# Track_em_V0_1.net
KiCad netlist of a schematic drawn in EAGLE
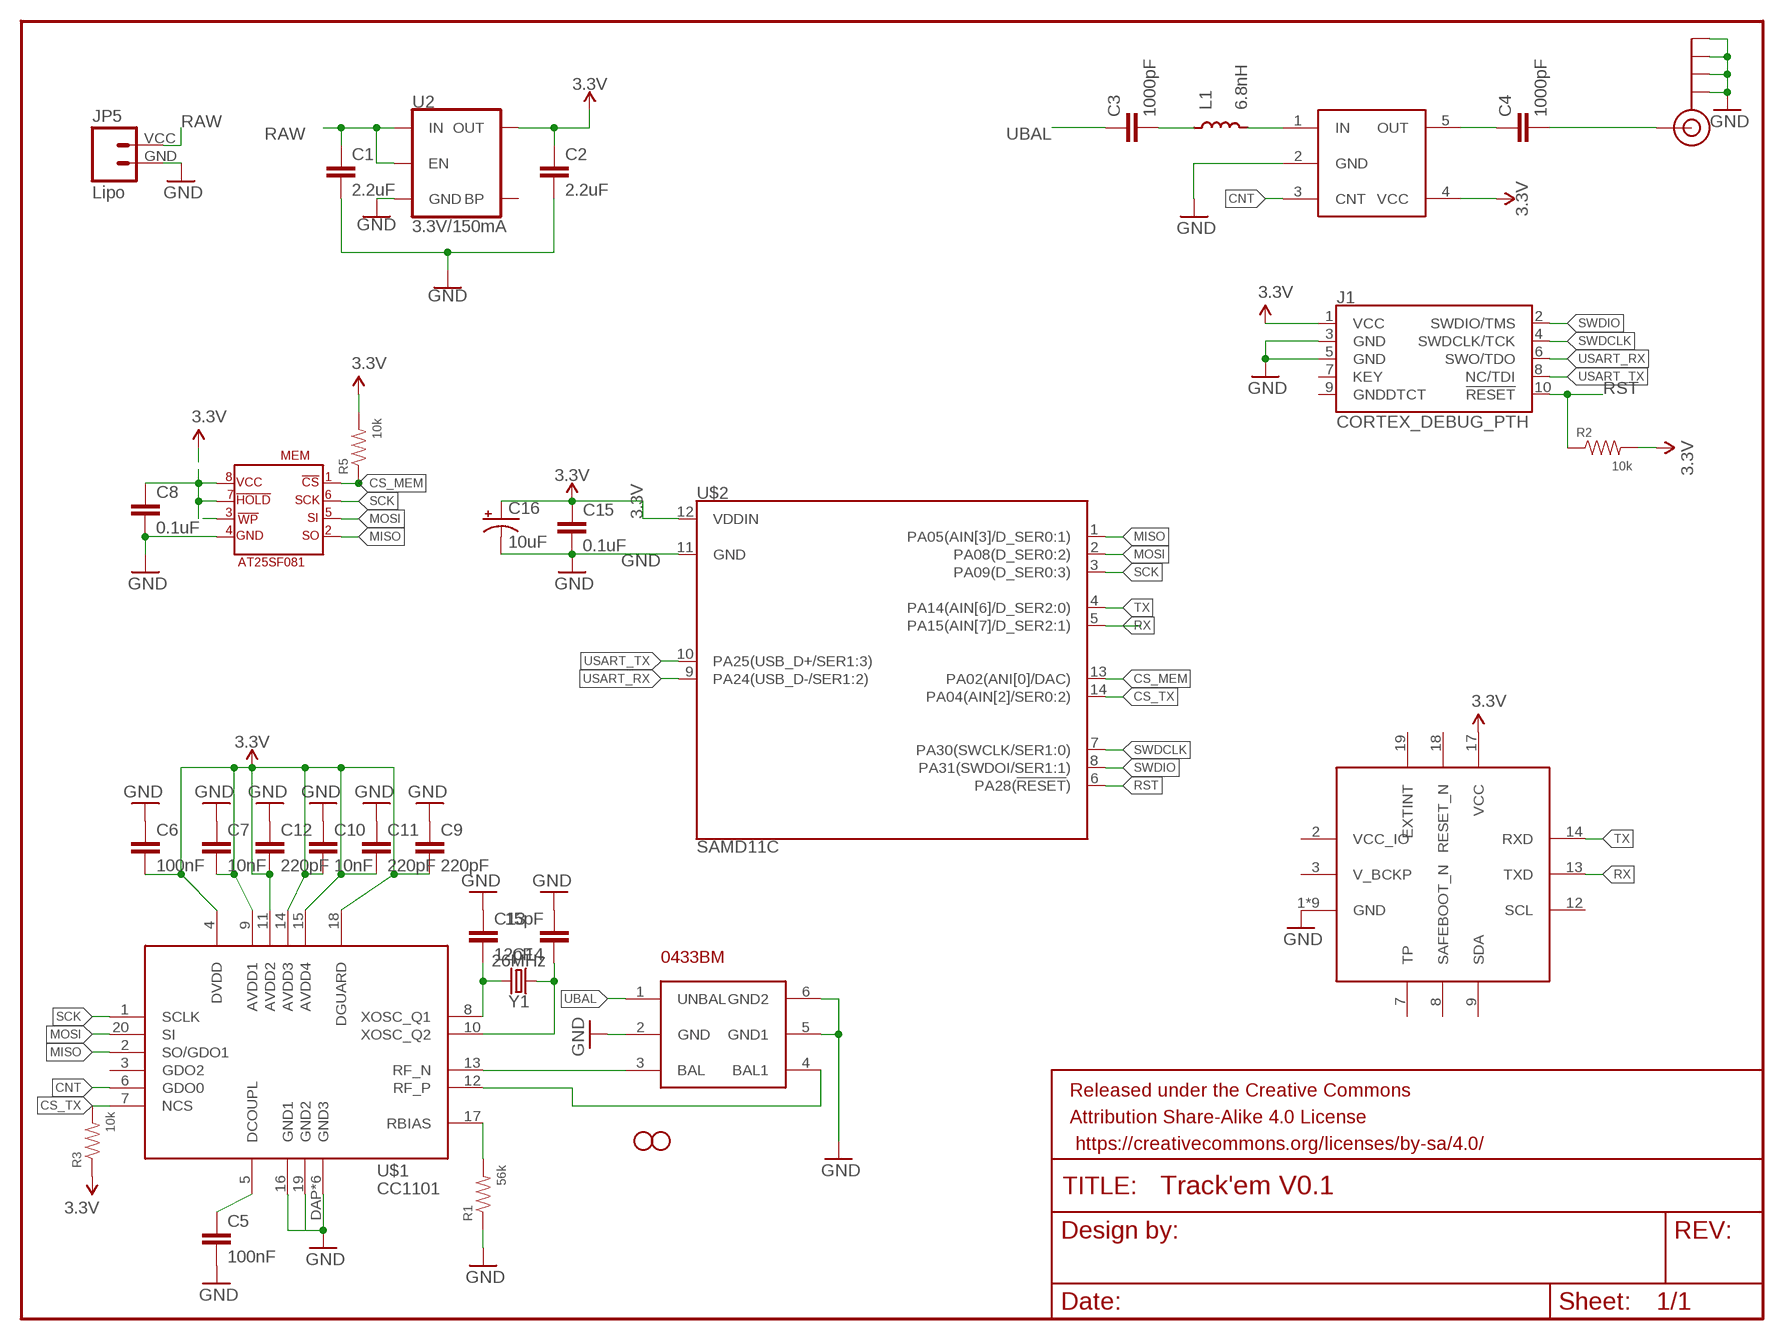
[diagram p0: schematic, sheet 1]

(export (version "E")
  (design (tool "Eeschema 10.0.6"))
  (components
    (comp (ref "C1")
      (value "2.2uF")
      (footprint "eagle-import:0603")
      (libsource (lib "eagle-import") (part "2.2UF-0603-10V-20%"))
    )
    (comp (ref "C2")
      (value "2.2uF")
      (footprint "eagle-import:0603")
      (libsource (lib "eagle-import") (part "2.2UF-0603-10V-20%"))
    )
    (comp (ref "C3")
      (value "1000pF")
      (footprint "eagle-import:0603")
      (libsource (lib "eagle-import") (part "2.2UF-0603-10V-20%"))
    )
    (comp (ref "C4")
      (value "1000pF")
      (footprint "eagle-import:0603")
      (libsource (lib "eagle-import") (part "2.2UF-0603-10V-20%"))
    )
    (comp (ref "C5")
      (value "100nF")
      (footprint "eagle-import:0402")
      (libsource (lib "eagle-import") (part "0.1UF-0402-16V-10%"))
    )
    (comp (ref "C6")
      (value "100nF")
      (footprint "eagle-import:0402")
      (libsource (lib "eagle-import") (part "0.1UF-0402-16V-10%"))
    )
    (comp (ref "C7")
      (value "10nF")
      (footprint "eagle-import:0402")
      (libsource (lib "eagle-import") (part "0.1UF-0402-16V-10%"))
    )
    (comp (ref "C8")
      (value "0.1uF")
      (footprint "eagle-import:0402")
      (libsource (lib "eagle-import") (part "0.1UF-0402-16V-10%"))
    )
    (comp (ref "C9")
      (value "220pF")
      (footprint "eagle-import:0402")
      (libsource (lib "eagle-import") (part "0.1UF-0402-16V-10%"))
    )
    (comp (ref "C10")
      (value "10nF")
      (footprint "eagle-import:0402")
      (libsource (lib "eagle-import") (part "0.1UF-0402-16V-10%"))
    )
    (comp (ref "C11")
      (value "220pF")
      (footprint "eagle-import:0402")
      (libsource (lib "eagle-import") (part "0.1UF-0402-16V-10%"))
    )
    (comp (ref "C12")
      (value "220pF")
      (footprint "eagle-import:0402")
      (libsource (lib "eagle-import") (part "0.1UF-0402-16V-10%"))
    )
    (comp (ref "C13")
      (value "12pF")
      (footprint "eagle-import:0402")
      (libsource (lib "eagle-import") (part "0.1UF-0402-16V-10%"))
    )
    (comp (ref "C14")
      (value "15pF")
      (footprint "eagle-import:0402")
      (libsource (lib "eagle-import") (part "0.1UF-0402-16V-10%"))
    )
    (comp (ref "C15")
      (value "0.1uF")
      (footprint "eagle-import:0402")
      (libsource (lib "eagle-import") (part "0.1UF-0402-16V-10%"))
    )
    (comp (ref "C16")
      (value "10uF")
      (footprint "eagle-import:0603-POL")
      (libsource (lib "eagle-import") (part "10UF-6.3V-20%(0603)(TANT){dblquote}"))
    )
    (comp (ref "FRAME1")
      (value "FRAME-LETTERNO_PACKAGE")
      (footprint "eagle-import:DUMMY")
      (fields (field (name "DESIGNER") "Nobody"))
      (libsource (lib "eagle-import") (part "FRAME-LETTERNO_PACKAGE"))
    )
    (comp (ref "H1")
      (value "STAND-OFFTIGHT")
      (footprint "eagle-import:STAND-OFF-TIGHT")
      (libsource (lib "eagle-import") (part "STAND-OFFTIGHT"))
    )
    (comp (ref "H2")
      (value "STAND-OFFTIGHT")
      (footprint "eagle-import:STAND-OFF-TIGHT")
      (libsource (lib "eagle-import") (part "STAND-OFFTIGHT"))
    )
    (comp (ref "IC1")
      (value "SAM-M8Q")
      (footprint "eagle-import:SAM-M8Q")
      (libsource (lib "eagle-import") (part "SAM-M8Q"))
    )
    (comp (ref "J$1")
      (value "SMA_EDGE")
      (footprint "eagle-import:SMA-EDGE")
      (libsource (lib "eagle-import") (part "SMA_EDGE"))
    )
    (comp (ref "J1")
      (value "CORTEX_DEBUG_PTH")
      (footprint "eagle-import:2X5-PTH-1.27MM")
      (libsource (lib "eagle-import") (part "CORTEX_DEBUG_PTH"))
    )
    (comp (ref "JP5")
      (value "Lipo")
      (footprint "eagle-import:JST-2-SMD-VERT")
      (libsource (lib "eagle-import") (part "M024UCON-15767"))
    )
    (comp (ref "L1")
      (value "6.8nH")
      (footprint "eagle-import:0603")
      (libsource (lib "eagle-import") (part "INDUCTOR0603"))
    )
    (comp (ref "MEM")
      (value "AT25SF081")
      (footprint "eagle-import:AT25SF081")
      (libsource (lib "eagle-import") (part "AT25SF081"))
    )
    (comp (ref "R1")
      (value "56k")
      (footprint "eagle-import:0402")
      (libsource (lib "eagle-import") (part "RESISTOR0402"))
    )
    (comp (ref "R2")
      (value "10k")
      (footprint "eagle-import:0402")
      (libsource (lib "eagle-import") (part "RESISTOR0402"))
    )
    (comp (ref "R3")
      (value "10k")
      (footprint "eagle-import:0402")
      (libsource (lib "eagle-import") (part "RESISTOR0402"))
    )
    (comp (ref "R5")
      (value "10k")
      (footprint "eagle-import:0402")
      (libsource (lib "eagle-import") (part "RESISTOR0402"))
    )
    (comp (ref "U$1")
      (value "CC1101")
      (footprint "eagle-import:CC1101")
      (libsource (lib "eagle-import") (part "CC1101"))
    )
    (comp (ref "U$2")
      (value "SAMD11C")
      (footprint "eagle-import:SAMD11C")
      (libsource (lib "eagle-import") (part "SAMD11C"))
    )
    (comp (ref "U$3")
      (value "0433BM15A0001")
      (footprint "eagle-import:0433BM15A0001")
      (libsource (lib "eagle-import") (part "0433BM15A0001"))
    )
    (comp (ref "U$4")
      (value "AN26018A")
      (footprint "eagle-import:AN26018A")
      (libsource (lib "eagle-import") (part "AN26018A"))
    )
    (comp (ref "U2")
      (value "3.3V/150mA")
      (footprint "eagle-import:SOT23-5")
      (libsource (lib "eagle-import") (part "V_REG_MIC52053.3V"))
    )
    (comp (ref "Y1")
      (value "26MHz")
      (footprint "eagle-import:CRYSTAL-SMD-3.2X2.5MM")
      (libsource (lib "eagle-import") (part "CRYSTALSMD-3.2X2.5"))
    )
  )
  (nets
    (net (code "1") (name "/RAW") (class "Default")
      (node (ref "C1") (pin "1") (pinfunction "1_1") (pintype "passive"))
      (node (ref "JP5") (pin "VCC") (pinfunction "2_VCC") (pintype "passive"))
      (node (ref "U2") (pin "1") (pinfunction "IN_1") (pintype "input"))
      (node (ref "U2") (pin "3") (pinfunction "EN_3") (pintype "input"))
    )
    (net (code "2") (name "3.3V") (class "Default")
      (node (ref "C10") (pin "2") (pinfunction "2_2") (pintype "passive"))
      (node (ref "C11") (pin "2") (pinfunction "2_2") (pintype "passive"))
      (node (ref "C12") (pin "2") (pinfunction "2_2") (pintype "passive"))
      (node (ref "C15") (pin "1") (pinfunction "1_1") (pintype "passive"))
      (node (ref "C16") (pin "A") (pinfunction "+_A") (pintype "passive"))
      (node (ref "C2") (pin "1") (pinfunction "1_1") (pintype "passive"))
      (node (ref "C6") (pin "2") (pinfunction "2_2") (pintype "passive"))
      (node (ref "C7") (pin "2") (pinfunction "2_2") (pintype "passive"))
      (node (ref "C8") (pin "1") (pinfunction "1_1") (pintype "passive"))
      (node (ref "C9") (pin "2") (pinfunction "2_2") (pintype "passive"))
      (node (ref "IC1") (pin "17") (pinfunction "VCC_17") (pintype "bidirectional"))
      (node (ref "J1") (pin "1") (pinfunction "VCC_1") (pintype "bidirectional"))
      (node (ref "MEM") (pin "!HOLD") (pinfunction "~{HOLD}_!HOLD") (pintype "bidirectional"))
      (node (ref "MEM") (pin "!WP") (pinfunction "~{WP}_!WP") (pintype "bidirectional"))
      (node (ref "MEM") (pin "VCC") (pinfunction "VCC_VCC") (pintype "bidirectional"))
      (node (ref "R2") (pin "2") (pinfunction "2_2") (pintype "passive"))
      (node (ref "R3") (pin "1") (pinfunction "1_1") (pintype "passive"))
      (node (ref "R5") (pin "2") (pinfunction "2_2") (pintype "passive"))
      (node (ref "U$1") (pin "11") (pinfunction "AVDD2_11") (pintype "bidirectional"))
      (node (ref "U$1") (pin "14") (pinfunction "AVDD3_14") (pintype "bidirectional"))
      (node (ref "U$1") (pin "15") (pinfunction "AVDD4_15") (pintype "bidirectional"))
      (node (ref "U$1") (pin "18") (pinfunction "DGUARD_18") (pintype "bidirectional"))
      (node (ref "U$1") (pin "4") (pinfunction "DVDD_4") (pintype "bidirectional"))
      (node (ref "U$1") (pin "9") (pinfunction "AVDD1_9") (pintype "bidirectional"))
      (node (ref "U$2") (pin "12") (pinfunction "VDDIN_12") (pintype "bidirectional"))
      (node (ref "U$4") (pin "4") (pinfunction "VCC_4") (pintype "bidirectional"))
      (node (ref "U2") (pin "5") (pinfunction "OUT_5") (pintype "passive"))
    )
    (net (code "3") (name "CNT") (class "Default")
      (node (ref "U$1") (pin "6") (pinfunction "GDO0_6") (pintype "bidirectional"))
      (node (ref "U$4") (pin "3") (pinfunction "CNT_3") (pintype "bidirectional"))
    )
    (net (code "4") (name "CS_MEM") (class "Default")
      (node (ref "MEM") (pin "!CS") (pinfunction "~{CS}_!CS") (pintype "bidirectional"))
      (node (ref "R5") (pin "1") (pinfunction "1_1") (pintype "passive"))
      (node (ref "U$2") (pin "13") (pinfunction "PA02(ANI[0]/DAC)_13") (pintype "bidirectional"))
    )
    (net (code "5") (name "CS_TX") (class "Default")
      (node (ref "R3") (pin "2") (pinfunction "2_2") (pintype "passive"))
      (node (ref "U$1") (pin "7") (pinfunction "NCS_7") (pintype "bidirectional"))
      (node (ref "U$2") (pin "14") (pinfunction "PA04(AIN[2]/SER0:2)_14") (pintype "bidirectional"))
    )
    (net (code "6") (name "GND") (class "Default")
      (node (ref "C1") (pin "2") (pinfunction "2_2") (pintype "passive"))
      (node (ref "C10") (pin "1") (pinfunction "1_1") (pintype "passive"))
      (node (ref "C11") (pin "1") (pinfunction "1_1") (pintype "passive"))
      (node (ref "C12") (pin "1") (pinfunction "1_1") (pintype "passive"))
      (node (ref "C13") (pin "1") (pinfunction "1_1") (pintype "passive"))
      (node (ref "C14") (pin "2") (pinfunction "2_2") (pintype "passive"))
      (node (ref "C15") (pin "2") (pinfunction "2_2") (pintype "passive"))
      (node (ref "C16") (pin "K") (pinfunction "-_K") (pintype "passive"))
      (node (ref "C2") (pin "2") (pinfunction "2_2") (pintype "passive"))
      (node (ref "C5") (pin "2") (pinfunction "2_2") (pintype "passive"))
      (node (ref "C6") (pin "1") (pinfunction "1_1") (pintype "passive"))
      (node (ref "C7") (pin "1") (pinfunction "1_1") (pintype "passive"))
      (node (ref "C8") (pin "2") (pinfunction "2_2") (pintype "passive"))
      (node (ref "C9") (pin "1") (pinfunction "1_1") (pintype "passive"))
      (node (ref "IC1") (pin "1") (pinfunction "GND_1") (pintype "bidirectional"))
      (node (ref "IC1") (pin "10") (pinfunction "GND_10") (pintype "bidirectional"))
      (node (ref "IC1") (pin "11") (pinfunction "GND_11") (pintype "bidirectional"))
      (node (ref "IC1") (pin "15") (pinfunction "GND_15") (pintype "bidirectional"))
      (node (ref "IC1") (pin "16") (pinfunction "GND_16") (pintype "bidirectional"))
      (node (ref "IC1") (pin "20") (pinfunction "GND_20") (pintype "bidirectional"))
      (node (ref "IC1") (pin "4") (pinfunction "GND_4") (pintype "bidirectional"))
      (node (ref "IC1") (pin "5") (pinfunction "GND_5") (pintype "bidirectional"))
      (node (ref "IC1") (pin "6") (pinfunction "GND_6") (pintype "bidirectional"))
      (node (ref "J$1") (pin "GND@0") (pinfunction "GND_GND@0") (pintype "bidirectional"))
      (node (ref "J$1") (pin "GND@1") (pinfunction "GND_GND@1") (pintype "bidirectional"))
      (node (ref "J$1") (pin "GND@2") (pinfunction "GND_GND@2") (pintype "bidirectional"))
      (node (ref "J$1") (pin "GND@3") (pinfunction "GND_GND@3") (pintype "bidirectional"))
      (node (ref "J1") (pin "3") (pinfunction "GND_3") (pintype "bidirectional"))
      (node (ref "J1") (pin "5") (pinfunction "GND_5") (pintype "bidirectional"))
      (node (ref "JP5") (pin "GND") (pinfunction "1_GND") (pintype "passive"))
      (node (ref "MEM") (pin "GND") (pinfunction "GND_GND") (pintype "bidirectional"))
      (node (ref "R1") (pin "1") (pinfunction "1_1") (pintype "passive"))
      (node (ref "U$1") (pin "16") (pinfunction "GND1_16") (pintype "bidirectional"))
      (node (ref "U$1") (pin "19") (pinfunction "GND2_19") (pintype "bidirectional"))
      (node (ref "U$1") (pin "DAP") (pinfunction "GND3_DAP") (pintype "bidirectional"))
      (node (ref "U$1") (pin "P$1") (pinfunction "GND3_P$1") (pintype "bidirectional"))
      (node (ref "U$1") (pin "P$2") (pinfunction "GND3_P$2") (pintype "bidirectional"))
      (node (ref "U$1") (pin "P$3") (pinfunction "GND3_P$3") (pintype "bidirectional"))
      (node (ref "U$1") (pin "P$4") (pinfunction "GND3_P$4") (pintype "bidirectional"))
      (node (ref "U$1") (pin "P$5") (pinfunction "GND3_P$5") (pintype "bidirectional"))
      (node (ref "U$2") (pin "11") (pinfunction "GND_11") (pintype "bidirectional"))
      (node (ref "U$3") (pin "2") (pinfunction "GND_2") (pintype "bidirectional"))
      (node (ref "U$3") (pin "5") (pinfunction "GND1_5") (pintype "bidirectional"))
      (node (ref "U$3") (pin "6") (pinfunction "GND2_6") (pintype "bidirectional"))
      (node (ref "U$4") (pin "2") (pinfunction "GND_2") (pintype "bidirectional"))
      (node (ref "U2") (pin "2") (pinfunction "GND_2") (pintype "input"))
    )
    (net (code "7") (name "MISO") (class "Default")
      (node (ref "MEM") (pin "SO") (pinfunction "SO_SO") (pintype "bidirectional"))
      (node (ref "U$1") (pin "2") (pinfunction "SO/GDO1_2") (pintype "bidirectional"))
      (node (ref "U$2") (pin "1") (pinfunction "PA05(AIN[3]/D_SER0:1)_1") (pintype "bidirectional"))
    )
    (net (code "8") (name "MOSI") (class "Default")
      (node (ref "MEM") (pin "SI") (pinfunction "SI_SI") (pintype "bidirectional"))
      (node (ref "U$1") (pin "20") (pinfunction "SI_20") (pintype "bidirectional"))
      (node (ref "U$2") (pin "2") (pinfunction "PA08(D_SER0:2)_2") (pintype "bidirectional"))
    )
    (net (code "9") (name "Net-(C3-Pad2)") (class "Default")
      (node (ref "C3") (pin "2") (pinfunction "2_2") (pintype "passive"))
      (node (ref "L1") (pin "1") (pinfunction "1_1") (pintype "passive"))
    )
    (net (code "10") (name "Net-(J$1-SIGNAL)") (class "Default")
      (node (ref "C4") (pin "2") (pinfunction "2_2") (pintype "passive"))
      (node (ref "J$1") (pin "SIG") (pinfunction "SIGNAL_SIG") (pintype "bidirectional"))
    )
    (net (code "11") (name "Net-(U$1-DCOUPL)") (class "Default")
      (node (ref "C5") (pin "1") (pinfunction "1_1") (pintype "passive"))
      (node (ref "U$1") (pin "5") (pinfunction "DCOUPL_5") (pintype "bidirectional"))
    )
    (net (code "12") (name "Net-(U$1-RBIAS)") (class "Default")
      (node (ref "R1") (pin "2") (pinfunction "2_2") (pintype "passive"))
      (node (ref "U$1") (pin "17") (pinfunction "RBIAS_17") (pintype "bidirectional"))
    )
    (net (code "13") (name "Net-(U$1-RF_N)") (class "Default")
      (node (ref "U$1") (pin "13") (pinfunction "RF_N_13") (pintype "bidirectional"))
      (node (ref "U$3") (pin "3") (pinfunction "BAL_3") (pintype "bidirectional"))
    )
    (net (code "14") (name "Net-(U$1-RF_P)") (class "Default")
      (node (ref "U$1") (pin "12") (pinfunction "RF_P_12") (pintype "bidirectional"))
      (node (ref "U$3") (pin "4") (pinfunction "BAL1_4") (pintype "bidirectional"))
    )
    (net (code "15") (name "Net-(U$1-XOSC_Q1)") (class "Default")
      (node (ref "C13") (pin "2") (pinfunction "2_2") (pintype "passive"))
      (node (ref "U$1") (pin "8") (pinfunction "XOSC_Q1_8") (pintype "bidirectional"))
      (node (ref "Y1") (pin "3") (pinfunction "2_3") (pintype "passive"))
    )
    (net (code "16") (name "Net-(U$1-XOSC_Q2)") (class "Default")
      (node (ref "C14") (pin "1") (pinfunction "1_1") (pintype "passive"))
      (node (ref "U$1") (pin "10") (pinfunction "XOSC_Q2_10") (pintype "bidirectional"))
      (node (ref "Y1") (pin "1") (pinfunction "1_1") (pintype "passive"))
    )
    (net (code "17") (name "Net-(U$4-IN)") (class "Default")
      (node (ref "L1") (pin "2") (pinfunction "2_2") (pintype "passive"))
      (node (ref "U$4") (pin "1") (pinfunction "IN_1") (pintype "bidirectional"))
    )
    (net (code "18") (name "Net-(U$4-OUT)") (class "Default")
      (node (ref "C4") (pin "1") (pinfunction "1_1") (pintype "passive"))
      (node (ref "U$4") (pin "5") (pinfunction "OUT_5") (pintype "bidirectional"))
    )
    (net (code "19") (name "RST") (class "Default")
      (node (ref "J1") (pin "10") (pinfunction "~{RESET}_10") (pintype "bidirectional"))
      (node (ref "R2") (pin "1") (pinfunction "1_1") (pintype "passive"))
      (node (ref "U$2") (pin "6") (pinfunction "PA28(~{RESET})_6") (pintype "bidirectional"))
    )
    (net (code "20") (name "RX") (class "Default")
      (node (ref "IC1") (pin "13") (pinfunction "TXD_13") (pintype "bidirectional"))
      (node (ref "U$2") (pin "5") (pinfunction "PA15(AIN[7]/D_SER2:1)_5") (pintype "bidirectional"))
    )
    (net (code "21") (name "SCK") (class "Default")
      (node (ref "MEM") (pin "SCK") (pinfunction "SCK_SCK") (pintype "bidirectional"))
      (node (ref "U$1") (pin "1") (pinfunction "SCLK_1") (pintype "bidirectional"))
      (node (ref "U$2") (pin "3") (pinfunction "PA09(D_SER0:3)_3") (pintype "bidirectional"))
    )
    (net (code "22") (name "SWDCLK") (class "Default")
      (node (ref "J1") (pin "4") (pinfunction "SWDCLK/TCK_4") (pintype "bidirectional"))
      (node (ref "U$2") (pin "7") (pinfunction "PA30(SWCLK/SER1:0)_7") (pintype "bidirectional"))
    )
    (net (code "23") (name "SWDIO") (class "Default")
      (node (ref "J1") (pin "2") (pinfunction "SWDIO/TMS_2") (pintype "bidirectional"))
      (node (ref "U$2") (pin "8") (pinfunction "PA31(SWDOI/SER1:1)_8") (pintype "bidirectional"))
    )
    (net (code "24") (name "TX") (class "Default")
      (node (ref "IC1") (pin "14") (pinfunction "RXD_14") (pintype "bidirectional"))
      (node (ref "U$2") (pin "4") (pinfunction "PA14(AIN[6]/D_SER2:0)_4") (pintype "bidirectional"))
    )
    (net (code "25") (name "UBAL") (class "Default")
      (node (ref "C3") (pin "1") (pinfunction "1_1") (pintype "passive"))
      (node (ref "U$3") (pin "1") (pinfunction "UNBAL_1") (pintype "bidirectional"))
    )
    (net (code "26") (name "USART_RX") (class "Default")
      (node (ref "J1") (pin "6") (pinfunction "SWO/TDO_6") (pintype "bidirectional"))
      (node (ref "U$2") (pin "9") (pinfunction "PA24(USB_D-/SER1:2)_9") (pintype "bidirectional"))
    )
    (net (code "27") (name "USART_TX") (class "Default")
      (node (ref "J1") (pin "8") (pinfunction "NC/TDI_8") (pintype "bidirectional"))
      (node (ref "U$2") (pin "10") (pinfunction "PA25(USB_D+/SER1:3)_10") (pintype "bidirectional"))
    )
    (net (code "28") (name "unconnected-(IC1-EXTINT-Pad19)") (class "Default")
      (node (ref "IC1") (pin "19") (pinfunction "EXTINT_19") (pintype "bidirectional"))
    )
    (net (code "29") (name "unconnected-(IC1-RESET_N-Pad18)") (class "Default")
      (node (ref "IC1") (pin "18") (pinfunction "RESET_N_18") (pintype "bidirectional"))
    )
    (net (code "30") (name "unconnected-(IC1-SAFEBOOT_N-Pad8)") (class "Default")
      (node (ref "IC1") (pin "8") (pinfunction "SAFEBOOT_N_8") (pintype "bidirectional"))
    )
    (net (code "31") (name "unconnected-(IC1-SCL-Pad12)") (class "Default")
      (node (ref "IC1") (pin "12") (pinfunction "SCL_12") (pintype "bidirectional"))
    )
    (net (code "32") (name "unconnected-(IC1-SDA-Pad9)") (class "Default")
      (node (ref "IC1") (pin "9") (pinfunction "SDA_9") (pintype "bidirectional"))
    )
    (net (code "33") (name "unconnected-(IC1-TP-Pad7)") (class "Default")
      (node (ref "IC1") (pin "7") (pinfunction "TP_7") (pintype "bidirectional"))
    )
    (net (code "34") (name "unconnected-(IC1-VCC_IO-Pad2)") (class "Default")
      (node (ref "IC1") (pin "2") (pinfunction "VCC_IO_2") (pintype "bidirectional"))
    )
    (net (code "35") (name "unconnected-(IC1-V_BCKP-Pad3)") (class "Default")
      (node (ref "IC1") (pin "3") (pinfunction "V_BCKP_3") (pintype "bidirectional"))
    )
    (net (code "36") (name "unconnected-(J1-GNDDTCT-Pad9)") (class "Default")
      (node (ref "J1") (pin "9") (pinfunction "GNDDTCT_9") (pintype "bidirectional"))
    )
    (net (code "37") (name "unconnected-(J1-KEY-Pad7)") (class "Default")
      (node (ref "J1") (pin "7") (pinfunction "KEY_7") (pintype "bidirectional"))
    )
    (net (code "38") (name "unconnected-(U$1-GDO2-Pad3)") (class "Default")
      (node (ref "U$1") (pin "3") (pinfunction "GDO2_3") (pintype "bidirectional"))
    )
    (net (code "39") (name "unconnected-(U2-BP-Pad4)") (class "Default")
      (node (ref "U2") (pin "4") (pinfunction "BP_4") (pintype "input"))
    )
  )
)
